# miditransformer.net
KiCad netlist of a schematic drawn in EAGLE
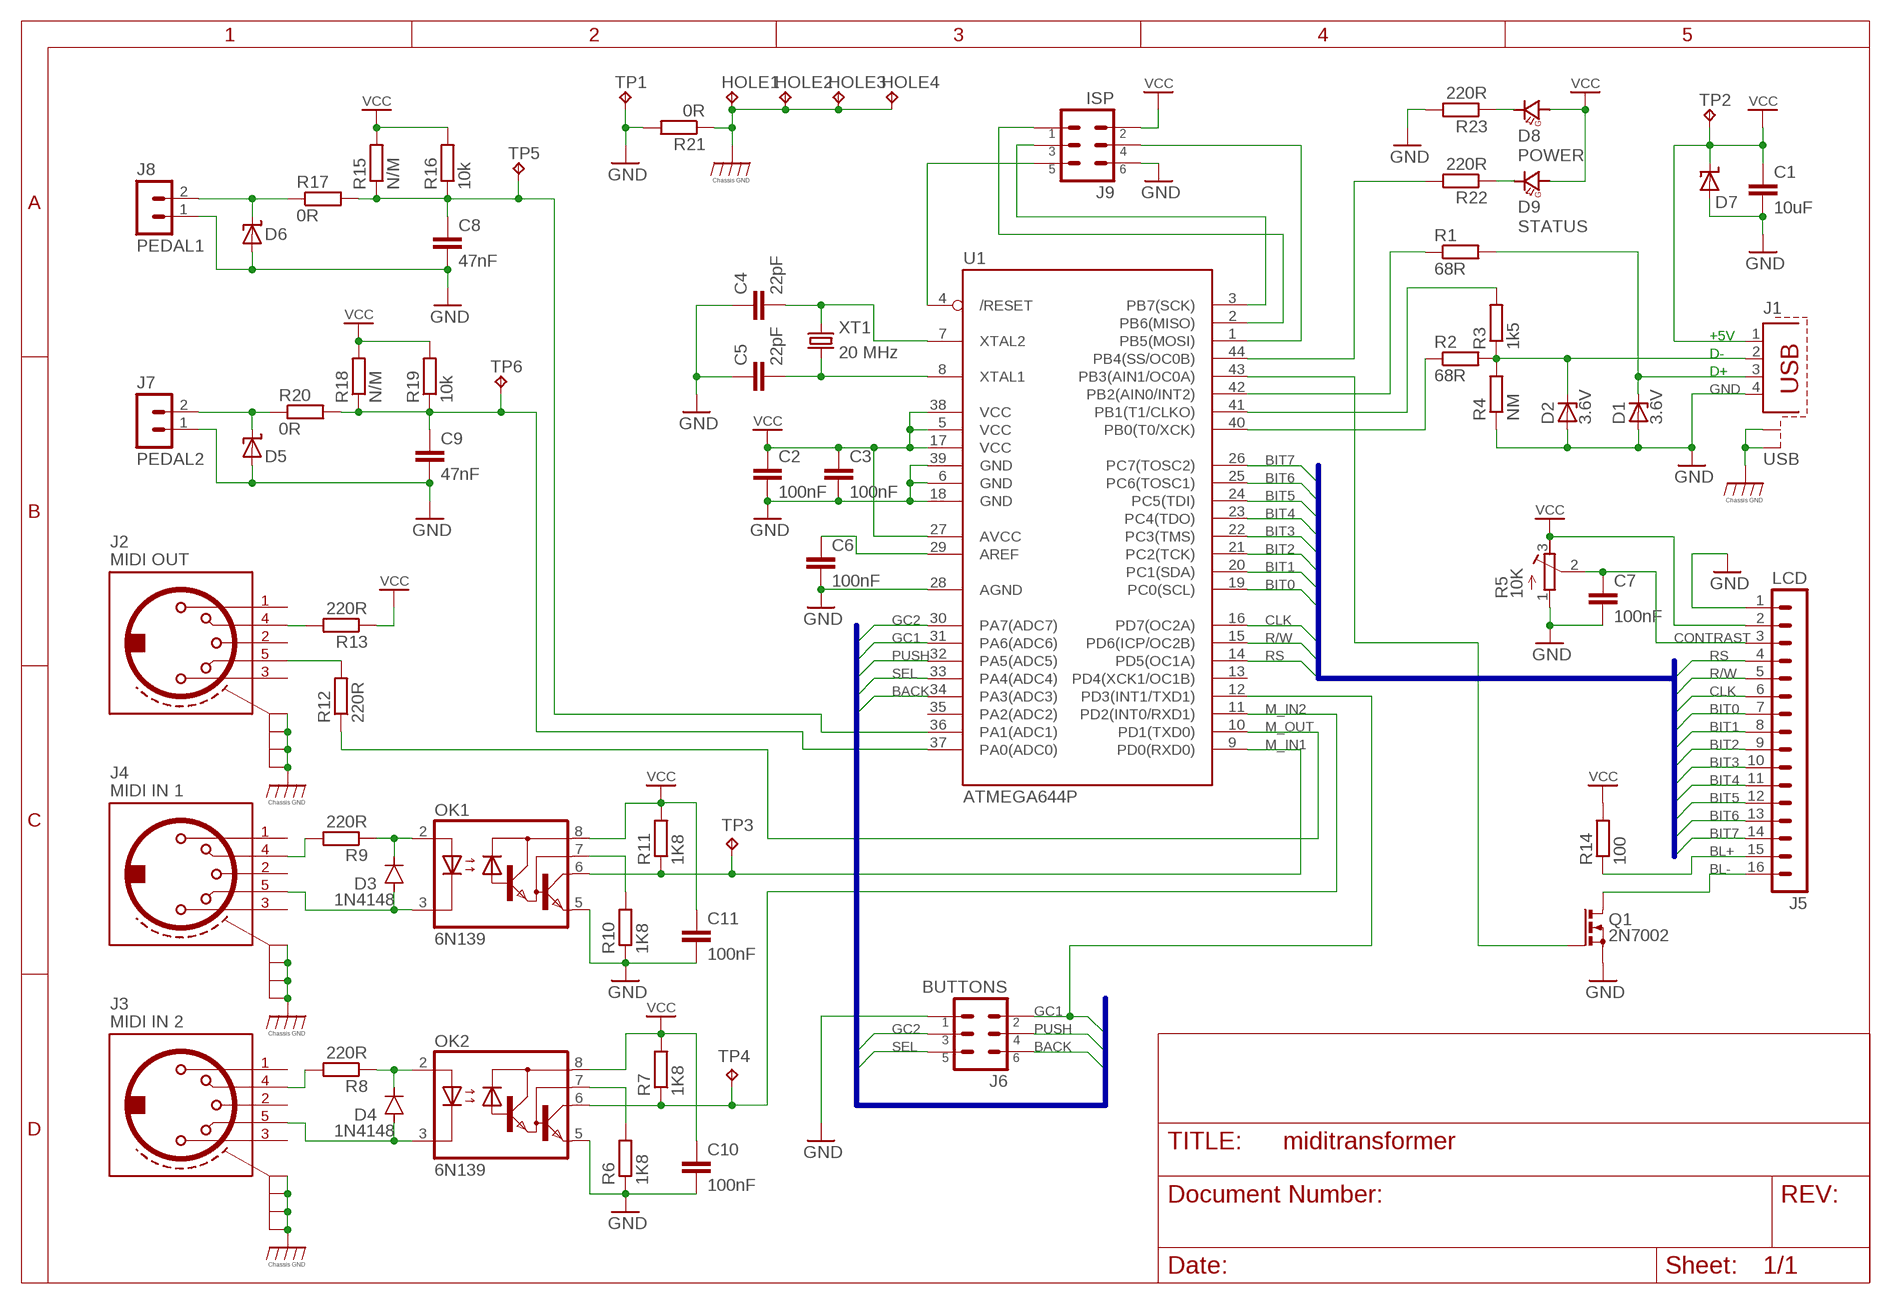
[diagram p0: schematic, sheet 1]

(export (version "E")
  (design (tool "Eeschema 10.0.6"))
  (components
    (comp (ref "C1")
      (value "10uF")
      (footprint "eagle-import:C1210")
      (libsource (lib "eagle-import") (part "C-EU_1210R"))
    )
    (comp (ref "C2")
      (value "100nF")
      (footprint "eagle-import:C0805")
      (libsource (lib "eagle-import") (part "C-EU_0805R"))
    )
    (comp (ref "C3")
      (value "100nF")
      (footprint "eagle-import:C0805")
      (libsource (lib "eagle-import") (part "C-EU_0805R"))
    )
    (comp (ref "C4")
      (value "22pF")
      (footprint "eagle-import:C0805")
      (libsource (lib "eagle-import") (part "C-EU_0805R"))
    )
    (comp (ref "C5")
      (value "22pF")
      (footprint "eagle-import:C0805")
      (libsource (lib "eagle-import") (part "C-EU_0805R"))
    )
    (comp (ref "C6")
      (value "100nF")
      (footprint "eagle-import:C0805")
      (libsource (lib "eagle-import") (part "C-EU_0805R"))
    )
    (comp (ref "C7")
      (value "100nF")
      (footprint "eagle-import:C0805")
      (libsource (lib "eagle-import") (part "C-EU_0805R"))
    )
    (comp (ref "C8")
      (value "47nF")
      (footprint "eagle-import:C0805")
      (libsource (lib "eagle-import") (part "C-EU_0805R"))
    )
    (comp (ref "C9")
      (value "47nF")
      (footprint "eagle-import:C0805")
      (libsource (lib "eagle-import") (part "C-EU_0805R"))
    )
    (comp (ref "C10")
      (value "100nF")
      (footprint "eagle-import:C0805")
      (libsource (lib "eagle-import") (part "C-EU_0805R"))
    )
    (comp (ref "C11")
      (value "100nF")
      (footprint "eagle-import:C0805")
      (libsource (lib "eagle-import") (part "C-EU_0805R"))
    )
    (comp (ref "D1")
      (value "3.6V")
      (footprint "eagle-import:DO34Z7")
      (libsource (lib "eagle-import") (part "ZENER-DIODEDO34-7"))
    )
    (comp (ref "D2")
      (value "3.6V")
      (footprint "eagle-import:DO34Z7")
      (libsource (lib "eagle-import") (part "ZENER-DIODEDO34-7"))
    )
    (comp (ref "D3")
      (value "1N4148")
      (footprint "eagle-import:MINIMELF")
      (libsource (lib "eagle-import") (part "1N4148MINIMELF"))
    )
    (comp (ref "D4")
      (value "1N4148")
      (footprint "eagle-import:MINIMELF")
      (libsource (lib "eagle-import") (part "1N4148MINIMELF"))
    )
    (comp (ref "D5")
      (value "SUPPRESSOR-SMB")
      (footprint "eagle-import:SMB")
      (libsource (lib "eagle-import") (part "SUPPRESSOR-SMB"))
    )
    (comp (ref "D6")
      (value "SUPPRESSOR-SMB")
      (footprint "eagle-import:SMB")
      (libsource (lib "eagle-import") (part "SUPPRESSOR-SMB"))
    )
    (comp (ref "D7")
      (value "SUPPRESSOR-SMB")
      (footprint "eagle-import:SMB")
      (libsource (lib "eagle-import") (part "SUPPRESSOR-SMB"))
    )
    (comp (ref "D8")
      (value "POWER")
      (footprint "eagle-import:LED3MM")
      (libsource (lib "eagle-import") (part "LTL-1CHG"))
    )
    (comp (ref "D9")
      (value "STATUS")
      (footprint "eagle-import:LED3MM")
      (libsource (lib "eagle-import") (part "LTL-1CHG"))
    )
    (comp (ref "HOLE1")
      (value "HOLE_PAD")
      (footprint "eagle-import:HOLE_PAD_3.2")
      (libsource (lib "eagle-import") (part "HOLE_PAD"))
    )
    (comp (ref "HOLE2")
      (value "HOLE_PAD")
      (footprint "eagle-import:HOLE_PAD_3.2")
      (libsource (lib "eagle-import") (part "HOLE_PAD"))
    )
    (comp (ref "HOLE3")
      (value "HOLE_PAD")
      (footprint "eagle-import:HOLE_PAD_3.2")
      (libsource (lib "eagle-import") (part "HOLE_PAD"))
    )
    (comp (ref "HOLE4")
      (value "HOLE_PAD")
      (footprint "eagle-import:HOLE_PAD_3.2")
      (libsource (lib "eagle-import") (part "HOLE_PAD"))
    )
    (comp (ref "J1")
      (value "USB")
      (footprint "eagle-import:PN61729-S")
      (libsource (lib "eagle-import") (part "PN61729-S"))
    )
    (comp (ref "J2")
      (value "MIDI OUT")
      (footprint "eagle-import:DIN5_FEM_UNIV")
      (libsource (lib "eagle-import") (part "DIN5_FEMALE_PCB"))
    )
    (comp (ref "J3")
      (value "MIDI IN 2")
      (footprint "eagle-import:DIN5_FEM_UNIV")
      (libsource (lib "eagle-import") (part "DIN5_FEMALE_PCB"))
    )
    (comp (ref "J4")
      (value "MIDI IN 1")
      (footprint "eagle-import:DIN5_FEM_UNIV")
      (libsource (lib "eagle-import") (part "DIN5_FEMALE_PCB"))
    )
    (comp (ref "J5")
      (value "LCD")
      (footprint "eagle-import:HDR_S_2X8")
      (libsource (lib "eagle-import") (part "HEADER2X8LS"))
    )
    (comp (ref "J6")
      (value "BUTTONS")
      (footprint "eagle-import:HDR_S_2X3")
      (libsource (lib "eagle-import") (part "con-head_HEADER2X3S"))
    )
    (comp (ref "J7")
      (value "PEDAL2")
      (footprint "eagle-import:MOLEX_KK_HDR2_FL")
      (libsource (lib "eagle-import") (part "HEADER1X2KK"))
    )
    (comp (ref "J8")
      (value "PEDAL1")
      (footprint "eagle-import:MOLEX_KK_HDR2_FL")
      (libsource (lib "eagle-import") (part "HEADER1X2KK"))
    )
    (comp (ref "J9")
      (value "ISP")
      (footprint "eagle-import:HDR_2X3")
      (libsource (lib "eagle-import") (part "HEADER2X3"))
    )
    (comp (ref "OK1")
      (value "6N139")
      (footprint "eagle-import:DIL08")
      (libsource (lib "eagle-import") (part "6N138DIL08"))
    )
    (comp (ref "OK2")
      (value "6N139")
      (footprint "eagle-import:DIL08")
      (libsource (lib "eagle-import") (part "6N138DIL08"))
    )
    (comp (ref "Q1")
      (value "2N7002")
      (footprint "eagle-import:SOT23")
      (libsource (lib "eagle-import") (part "2N700?2"))
    )
    (comp (ref "R1")
      (value "68R")
      (footprint "eagle-import:R0805")
      (libsource (lib "eagle-import") (part "R-EU0805"))
    )
    (comp (ref "R2")
      (value "68R")
      (footprint "eagle-import:R0805")
      (libsource (lib "eagle-import") (part "R-EU0805"))
    )
    (comp (ref "R3")
      (value "1k5")
      (footprint "eagle-import:R0805")
      (libsource (lib "eagle-import") (part "R-EU0805"))
    )
    (comp (ref "R4")
      (value "NM")
      (footprint "eagle-import:R0805")
      (libsource (lib "eagle-import") (part "R-EU0805"))
    )
    (comp (ref "R5")
      (value "10K")
      (footprint "eagle-import:RTRIM3339P")
      (libsource (lib "eagle-import") (part "R-TRIMM"))
    )
    (comp (ref "R6")
      (value "1K8")
      (footprint "eagle-import:R0805")
      (libsource (lib "eagle-import") (part "R-EU0805"))
    )
    (comp (ref "R7")
      (value "1K8")
      (footprint "eagle-import:R0805")
      (libsource (lib "eagle-import") (part "R-EU0805"))
    )
    (comp (ref "R8")
      (value "220R")
      (footprint "eagle-import:R0805")
      (libsource (lib "eagle-import") (part "R-EU0805"))
    )
    (comp (ref "R9")
      (value "220R")
      (footprint "eagle-import:R0805")
      (libsource (lib "eagle-import") (part "R-EU0805"))
    )
    (comp (ref "R10")
      (value "1K8")
      (footprint "eagle-import:R0805")
      (libsource (lib "eagle-import") (part "R-EU0805"))
    )
    (comp (ref "R11")
      (value "1K8")
      (footprint "eagle-import:R0805")
      (libsource (lib "eagle-import") (part "R-EU0805"))
    )
    (comp (ref "R12")
      (value "220R")
      (footprint "eagle-import:R0805")
      (libsource (lib "eagle-import") (part "R-EU0805"))
    )
    (comp (ref "R13")
      (value "220R")
      (footprint "eagle-import:R0805")
      (libsource (lib "eagle-import") (part "R-EU0805"))
    )
    (comp (ref "R14")
      (value "100")
      (footprint "eagle-import:0207_7")
      (libsource (lib "eagle-import") (part "R-EULEADED-7.5"))
    )
    (comp (ref "R15")
      (value "N/M")
      (footprint "eagle-import:R0805")
      (libsource (lib "eagle-import") (part "R-EU0805"))
    )
    (comp (ref "R16")
      (value "10k")
      (footprint "eagle-import:R0805")
      (libsource (lib "eagle-import") (part "R-EU0805"))
    )
    (comp (ref "R17")
      (value "0R")
      (footprint "eagle-import:R0805")
      (libsource (lib "eagle-import") (part "R-EU0805"))
    )
    (comp (ref "R18")
      (value "N/M")
      (footprint "eagle-import:R0805")
      (libsource (lib "eagle-import") (part "R-EU0805"))
    )
    (comp (ref "R19")
      (value "10k")
      (footprint "eagle-import:R0805")
      (libsource (lib "eagle-import") (part "R-EU0805"))
    )
    (comp (ref "R20")
      (value "0R")
      (footprint "eagle-import:R0805")
      (libsource (lib "eagle-import") (part "R-EU0805"))
    )
    (comp (ref "R21")
      (value "0R")
      (footprint "eagle-import:R0805")
      (libsource (lib "eagle-import") (part "R-EU0805"))
    )
    (comp (ref "R22")
      (value "220R")
      (footprint "eagle-import:R0805")
      (libsource (lib "eagle-import") (part "R-EU0805"))
    )
    (comp (ref "R23")
      (value "220R")
      (footprint "eagle-import:R0805")
      (libsource (lib "eagle-import") (part "R-EU0805"))
    )
    (comp (ref "TP1")
      (value "TPTH-15-06")
      (footprint "eagle-import:TP-TH-15-06")
      (libsource (lib "eagle-import") (part "TPTH-15-06"))
    )
    (comp (ref "TP2")
      (value "TPTH-15-06")
      (footprint "eagle-import:TP-TH-15-06")
      (libsource (lib "eagle-import") (part "TPTH-15-06"))
    )
    (comp (ref "TP3")
      (value "TPTH-15-06")
      (footprint "eagle-import:TP-TH-15-06")
      (libsource (lib "eagle-import") (part "TPTH-15-06"))
    )
    (comp (ref "TP4")
      (value "TPTH-15-06")
      (footprint "eagle-import:TP-TH-15-06")
      (libsource (lib "eagle-import") (part "TPTH-15-06"))
    )
    (comp (ref "TP5")
      (value "TPTH-15-06")
      (footprint "eagle-import:TP-TH-15-06")
      (libsource (lib "eagle-import") (part "TPTH-15-06"))
    )
    (comp (ref "TP6")
      (value "TPTH-15-06")
      (footprint "eagle-import:TP-TH-15-06")
      (libsource (lib "eagle-import") (part "TPTH-15-06"))
    )
    (comp (ref "U1")
      (value "ATMEGA644P")
      (footprint "eagle-import:TQFP44")
      (libsource (lib "eagle-import") (part "ATMEGA644P"))
    )
    (comp (ref "XT1")
      (value "20 MHz")
      (footprint "eagle-import:HC49")
      (libsource (lib "eagle-import") (part "XTAL_HC49"))
    )
  )
  (nets
    (net (code "1") (name "/BACK") (class "Default")
      (node (ref "J6") (pin "6") (pinfunction "6_6") (pintype "passive"))
      (node (ref "U1") (pin "34") (pinfunction "PA3(ADC3)_34") (pintype "bidirectional"))
    )
    (net (code "2") (name "/BIT0") (class "Default")
      (node (ref "J5") (pin "7") (pinfunction "7_7") (pintype "passive"))
      (node (ref "U1") (pin "19") (pinfunction "PC0(SCL)_19") (pintype "bidirectional"))
    )
    (net (code "3") (name "/BIT1") (class "Default")
      (node (ref "J5") (pin "8") (pinfunction "8_8") (pintype "passive"))
      (node (ref "U1") (pin "20") (pinfunction "PC1(SDA)_20") (pintype "bidirectional"))
    )
    (net (code "4") (name "/BIT2") (class "Default")
      (node (ref "J5") (pin "9") (pinfunction "9_9") (pintype "passive"))
      (node (ref "U1") (pin "21") (pinfunction "PC2(TCK)_21") (pintype "bidirectional"))
    )
    (net (code "5") (name "/BIT3") (class "Default")
      (node (ref "J5") (pin "10") (pinfunction "10_10") (pintype "passive"))
      (node (ref "U1") (pin "22") (pinfunction "PC3(TMS)_22") (pintype "bidirectional"))
    )
    (net (code "6") (name "/BIT4") (class "Default")
      (node (ref "J5") (pin "11") (pinfunction "11_11") (pintype "passive"))
      (node (ref "U1") (pin "23") (pinfunction "PC4(TDO)_23") (pintype "bidirectional"))
    )
    (net (code "7") (name "/BIT5") (class "Default")
      (node (ref "J5") (pin "12") (pinfunction "12_12") (pintype "passive"))
      (node (ref "U1") (pin "24") (pinfunction "PC5(TDI)_24") (pintype "bidirectional"))
    )
    (net (code "8") (name "/BIT6") (class "Default")
      (node (ref "J5") (pin "13") (pinfunction "13_13") (pintype "passive"))
      (node (ref "U1") (pin "25") (pinfunction "PC6(TOSC1)_25") (pintype "bidirectional"))
    )
    (net (code "9") (name "/BIT7") (class "Default")
      (node (ref "J5") (pin "14") (pinfunction "14_14") (pintype "passive"))
      (node (ref "U1") (pin "26") (pinfunction "PC7(TOSC2)_26") (pintype "bidirectional"))
    )
    (net (code "10") (name "/BL+") (class "Default")
      (node (ref "J5") (pin "15") (pinfunction "15_15") (pintype "passive"))
      (node (ref "R14") (pin "1") (pinfunction "1_1") (pintype "passive"))
    )
    (net (code "11") (name "/BL-") (class "Default")
      (node (ref "J5") (pin "16") (pinfunction "16_16") (pintype "passive"))
      (node (ref "Q1") (pin "3") (pinfunction "D_3") (pintype "passive"))
    )
    (net (code "12") (name "/CLK") (class "Default")
      (node (ref "J5") (pin "6") (pinfunction "6_6") (pintype "passive"))
      (node (ref "U1") (pin "16") (pinfunction "PD7(OC2A)_16") (pintype "bidirectional"))
    )
    (net (code "13") (name "/CONTRAST") (class "Default")
      (node (ref "C7") (pin "1") (pinfunction "1_1") (pintype "passive"))
      (node (ref "J5") (pin "3") (pinfunction "3_3") (pintype "passive"))
      (node (ref "R5") (pin "2") (pinfunction "S_2") (pintype "passive"))
    )
    (net (code "14") (name "/GC1") (class "Default")
      (node (ref "J6") (pin "2") (pinfunction "2_2") (pintype "passive"))
      (node (ref "U1") (pin "12") (pinfunction "PD3(INT1/TXD1)_12") (pintype "bidirectional"))
      (node (ref "U1") (pin "31") (pinfunction "PA6(ADC6)_31") (pintype "bidirectional"))
    )
    (net (code "15") (name "/GC2") (class "Default")
      (node (ref "J6") (pin "3") (pinfunction "3_3") (pintype "passive"))
      (node (ref "U1") (pin "30") (pinfunction "PA7(ADC7)_30") (pintype "bidirectional"))
    )
    (net (code "16") (name "/M_IN1") (class "Default")
      (node (ref "OK1") (pin "6") (pinfunction "VO_6") (pintype "passive"))
      (node (ref "R11") (pin "1") (pinfunction "1_1") (pintype "passive"))
      (node (ref "TP3") (pin "1") (pinfunction "TP_1") (pintype "input"))
      (node (ref "U1") (pin "9") (pinfunction "PD0(RXD0)_9") (pintype "bidirectional"))
    )
    (net (code "17") (name "/M_IN2") (class "Default")
      (node (ref "OK2") (pin "6") (pinfunction "VO_6") (pintype "passive"))
      (node (ref "R7") (pin "1") (pinfunction "1_1") (pintype "passive"))
      (node (ref "TP4") (pin "1") (pinfunction "TP_1") (pintype "input"))
      (node (ref "U1") (pin "11") (pinfunction "PD2(INT0/RXD1)_11") (pintype "bidirectional"))
    )
    (net (code "18") (name "/M_OUT") (class "Default")
      (node (ref "R12") (pin "1") (pinfunction "1_1") (pintype "passive"))
      (node (ref "U1") (pin "10") (pinfunction "PD1(TXD0)_10") (pintype "bidirectional"))
    )
    (net (code "19") (name "/PUSH") (class "Default")
      (node (ref "J6") (pin "4") (pinfunction "4_4") (pintype "passive"))
      (node (ref "U1") (pin "32") (pinfunction "PA5(ADC5)_32") (pintype "bidirectional"))
    )
    (net (code "20") (name "/RS") (class "Default")
      (node (ref "J5") (pin "4") (pinfunction "4_4") (pintype "passive"))
      (node (ref "U1") (pin "14") (pinfunction "PD5(OC1A)_14") (pintype "bidirectional"))
    )
    (net (code "21") (name "/R{slash}W") (class "Default")
      (node (ref "J5") (pin "5") (pinfunction "5_5") (pintype "passive"))
      (node (ref "U1") (pin "15") (pinfunction "PD6(ICP/OC2B)_15") (pintype "bidirectional"))
    )
    (net (code "22") (name "/SEL") (class "Default")
      (node (ref "J6") (pin "5") (pinfunction "5_5") (pintype "passive"))
      (node (ref "U1") (pin "33") (pinfunction "PA4(ADC4)_33") (pintype "bidirectional"))
    )
    (net (code "23") (name "CGND") (class "Default")
      (node (ref "HOLE1") (pin "P$0") (pinfunction "TP_P$0") (pintype "input"))
      (node (ref "HOLE2") (pin "P$0") (pinfunction "TP_P$0") (pintype "input"))
      (node (ref "HOLE3") (pin "P$0") (pinfunction "TP_P$0") (pintype "input"))
      (node (ref "HOLE4") (pin "P$0") (pinfunction "TP_P$0") (pintype "input"))
      (node (ref "J1") (pin "S1") (pinfunction "S1_S1") (pintype "passive"))
      (node (ref "J1") (pin "S2") (pinfunction "S2_S2") (pintype "passive"))
      (node (ref "J2") (pin "PE@1") (pinfunction "PE_PE@1") (pintype "power_in"))
      (node (ref "J2") (pin "PE@2") (pinfunction "PE_PE@2") (pintype "power_in"))
      (node (ref "J2") (pin "PE@3") (pinfunction "PE_PE@3") (pintype "power_in"))
      (node (ref "J2") (pin "PE@4") (pinfunction "PE_PE@4") (pintype "power_in"))
      (node (ref "J3") (pin "PE@1") (pinfunction "PE_PE@1") (pintype "power_in"))
      (node (ref "J3") (pin "PE@2") (pinfunction "PE_PE@2") (pintype "power_in"))
      (node (ref "J3") (pin "PE@3") (pinfunction "PE_PE@3") (pintype "power_in"))
      (node (ref "J3") (pin "PE@4") (pinfunction "PE_PE@4") (pintype "power_in"))
      (node (ref "J4") (pin "PE@1") (pinfunction "PE_PE@1") (pintype "power_in"))
      (node (ref "J4") (pin "PE@2") (pinfunction "PE_PE@2") (pintype "power_in"))
      (node (ref "J4") (pin "PE@3") (pinfunction "PE_PE@3") (pintype "power_in"))
      (node (ref "J4") (pin "PE@4") (pinfunction "PE_PE@4") (pintype "power_in"))
      (node (ref "R21") (pin "1") (pinfunction "1_1") (pintype "passive"))
    )
    (net (code "24") (name "GND") (class "Default")
      (node (ref "C1") (pin "2") (pinfunction "2_2") (pintype "passive"))
      (node (ref "C10") (pin "2") (pinfunction "2_2") (pintype "passive"))
      (node (ref "C11") (pin "2") (pinfunction "2_2") (pintype "passive"))
      (node (ref "C2") (pin "2") (pinfunction "2_2") (pintype "passive"))
      (node (ref "C3") (pin "2") (pinfunction "2_2") (pintype "passive"))
      (node (ref "C4") (pin "1") (pinfunction "1_1") (pintype "passive"))
      (node (ref "C5") (pin "1") (pinfunction "1_1") (pintype "passive"))
      (node (ref "C6") (pin "2") (pinfunction "2_2") (pintype "passive"))
      (node (ref "C7") (pin "2") (pinfunction "2_2") (pintype "passive"))
      (node (ref "C8") (pin "2") (pinfunction "2_2") (pintype "passive"))
      (node (ref "C9") (pin "2") (pinfunction "2_2") (pintype "passive"))
      (node (ref "D1") (pin "A") (pinfunction "A_A") (pintype "passive"))
      (node (ref "D2") (pin "A") (pinfunction "A_A") (pintype "passive"))
      (node (ref "D5") (pin "A") (pinfunction "A_A") (pintype "passive"))
      (node (ref "D6") (pin "A") (pinfunction "A_A") (pintype "passive"))
      (node (ref "D7") (pin "A") (pinfunction "A_A") (pintype "passive"))
      (node (ref "J1") (pin "4") (pinfunction "4_4") (pintype "passive"))
      (node (ref "J5") (pin "1") (pinfunction "1_1") (pintype "passive"))
      (node (ref "J6") (pin "1") (pinfunction "1_1") (pintype "passive"))
      (node (ref "J7") (pin "1") (pinfunction "1_1") (pintype "passive"))
      (node (ref "J8") (pin "1") (pinfunction "1_1") (pintype "passive"))
      (node (ref "J9") (pin "6") (pinfunction "6_6") (pintype "passive"))
      (node (ref "OK1") (pin "5") (pinfunction "GND_5") (pintype "passive"))
      (node (ref "OK2") (pin "5") (pinfunction "GND_5") (pintype "passive"))
      (node (ref "Q1") (pin "2") (pinfunction "S_2") (pintype "passive"))
      (node (ref "R10") (pin "1") (pinfunction "1_1") (pintype "passive"))
      (node (ref "R21") (pin "2") (pinfunction "2_2") (pintype "passive"))
      (node (ref "R23") (pin "2") (pinfunction "2_2") (pintype "passive"))
      (node (ref "R4") (pin "1") (pinfunction "1_1") (pintype "passive"))
      (node (ref "R5") (pin "1") (pinfunction "E_1") (pintype "passive"))
      (node (ref "R6") (pin "1") (pinfunction "1_1") (pintype "passive"))
      (node (ref "TP1") (pin "1") (pinfunction "TP_1") (pintype "input"))
      (node (ref "U1") (pin "18") (pinfunction "GND_18") (pintype "power_in"))
      (node (ref "U1") (pin "28") (pinfunction "AGND_28") (pintype "power_in"))
      (node (ref "U1") (pin "39") (pinfunction "GND_39") (pintype "power_in"))
      (node (ref "U1") (pin "6") (pinfunction "GND_6") (pintype "power_in"))
    )
    (net (code "25") (name "Net-(D1-PadC)") (class "Default")
      (node (ref "D1") (pin "C") (pinfunction "C_C") (pintype "passive"))
      (node (ref "J1") (pin "3") (pinfunction "3_3") (pintype "passive"))
      (node (ref "R1") (pin "2") (pinfunction "2_2") (pintype "passive"))
    )
    (net (code "26") (name "Net-(D2-PadC)") (class "Default")
      (node (ref "D2") (pin "C") (pinfunction "C_C") (pintype "passive"))
      (node (ref "J1") (pin "2") (pinfunction "2_2") (pintype "passive"))
      (node (ref "R2") (pin "2") (pinfunction "2_2") (pintype "passive"))
      (node (ref "R3") (pin "1") (pinfunction "1_1") (pintype "passive"))
      (node (ref "R4") (pin "2") (pinfunction "2_2") (pintype "passive"))
    )
    (net (code "27") (name "Net-(D5-PadC)") (class "Default")
      (node (ref "D5") (pin "C") (pinfunction "C_C") (pintype "passive"))
      (node (ref "J7") (pin "2") (pinfunction "2_2") (pintype "passive"))
      (node (ref "R20") (pin "1") (pinfunction "1_1") (pintype "passive"))
    )
    (net (code "28") (name "Net-(D6-PadC)") (class "Default")
      (node (ref "D6") (pin "C") (pinfunction "C_C") (pintype "passive"))
      (node (ref "J8") (pin "2") (pinfunction "2_2") (pintype "passive"))
      (node (ref "R17") (pin "1") (pinfunction "1_1") (pintype "passive"))
    )
    (net (code "29") (name "Net-(D8-PadC)") (class "Default")
      (node (ref "D8") (pin "C") (pinfunction "C_C") (pintype "passive"))
      (node (ref "R23") (pin "1") (pinfunction "1_1") (pintype "passive"))
    )
    (net (code "30") (name "Net-(D9-PadC)") (class "Default")
      (node (ref "D9") (pin "C") (pinfunction "C_C") (pintype "passive"))
      (node (ref "R22") (pin "1") (pinfunction "1_1") (pintype "passive"))
    )
    (net (code "31") (name "Net-(J2-Pad4)") (class "Default")
      (node (ref "J2") (pin "4") (pinfunction "4_4") (pintype "passive"))
      (node (ref "R13") (pin "2") (pinfunction "2_2") (pintype "passive"))
    )
    (net (code "32") (name "Net-(J2-Pad5)") (class "Default")
      (node (ref "J2") (pin "5") (pinfunction "5_5") (pintype "passive"))
      (node (ref "R12") (pin "2") (pinfunction "2_2") (pintype "passive"))
    )
    (net (code "33") (name "Net-(J3-Pad4)") (class "Default")
      (node (ref "J3") (pin "4") (pinfunction "4_4") (pintype "passive"))
      (node (ref "R8") (pin "2") (pinfunction "2_2") (pintype "passive"))
    )
    (net (code "34") (name "Net-(J4-Pad4)") (class "Default")
      (node (ref "J4") (pin "4") (pinfunction "4_4") (pintype "passive"))
      (node (ref "R9") (pin "2") (pinfunction "2_2") (pintype "passive"))
    )
    (net (code "35") (name "Net-(OK1-A)") (class "Default")
      (node (ref "D3") (pin "C") (pinfunction "C_C") (pintype "passive"))
      (node (ref "OK1") (pin "2") (pinfunction "A_2") (pintype "passive"))
      (node (ref "R9") (pin "1") (pinfunction "1_1") (pintype "passive"))
    )
    (net (code "36") (name "Net-(OK1-C)") (class "Default")
      (node (ref "D3") (pin "A") (pinfunction "A_A") (pintype "passive"))
      (node (ref "J4") (pin "5") (pinfunction "5_5") (pintype "passive"))
      (node (ref "OK1") (pin "3") (pinfunction "C_3") (pintype "passive"))
    )
    (net (code "37") (name "Net-(OK1-VB)") (class "Default")
      (node (ref "OK1") (pin "7") (pinfunction "VB_7") (pintype "passive"))
      (node (ref "R10") (pin "2") (pinfunction "2_2") (pintype "passive"))
    )
    (net (code "38") (name "Net-(OK2-A)") (class "Default")
      (node (ref "D4") (pin "C") (pinfunction "C_C") (pintype "passive"))
      (node (ref "OK2") (pin "2") (pinfunction "A_2") (pintype "passive"))
      (node (ref "R8") (pin "1") (pinfunction "1_1") (pintype "passive"))
    )
    (net (code "39") (name "Net-(OK2-C)") (class "Default")
      (node (ref "D4") (pin "A") (pinfunction "A_A") (pintype "passive"))
      (node (ref "J3") (pin "5") (pinfunction "5_5") (pintype "passive"))
      (node (ref "OK2") (pin "3") (pinfunction "C_3") (pintype "passive"))
    )
    (net (code "40") (name "Net-(OK2-VB)") (class "Default")
      (node (ref "OK2") (pin "7") (pinfunction "VB_7") (pintype "passive"))
      (node (ref "R6") (pin "2") (pinfunction "2_2") (pintype "passive"))
    )
    (net (code "41") (name "Net-(Q1-G)") (class "Default")
      (node (ref "Q1") (pin "1") (pinfunction "G_1") (pintype "passive"))
      (node (ref "U1") (pin "43") (pinfunction "PB3(AIN1/OC0A)_43") (pintype "bidirectional"))
    )
    (net (code "42") (name "Net-(TP5-TP)") (class "Default")
      (node (ref "C8") (pin "1") (pinfunction "1_1") (pintype "passive"))
      (node (ref "R15") (pin "1") (pinfunction "1_1") (pintype "passive"))
      (node (ref "R16") (pin "1") (pinfunction "1_1") (pintype "passive"))
      (node (ref "R17") (pin "2") (pinfunction "2_2") (pintype "passive"))
      (node (ref "TP5") (pin "1") (pinfunction "TP_1") (pintype "input"))
      (node (ref "U1") (pin "36") (pinfunction "PA1(ADC1)_36") (pintype "bidirectional"))
    )
    (net (code "43") (name "Net-(TP6-TP)") (class "Default")
      (node (ref "C9") (pin "1") (pinfunction "1_1") (pintype "passive"))
      (node (ref "R18") (pin "1") (pinfunction "1_1") (pintype "passive"))
      (node (ref "R19") (pin "1") (pinfunction "1_1") (pintype "passive"))
      (node (ref "R20") (pin "2") (pinfunction "2_2") (pintype "passive"))
      (node (ref "TP6") (pin "1") (pinfunction "TP_1") (pintype "input"))
      (node (ref "U1") (pin "37") (pinfunction "PA0(ADC0)_37") (pintype "bidirectional"))
    )
    (net (code "44") (name "Net-(U1-AREF)") (class "Default")
      (node (ref "C6") (pin "1") (pinfunction "1_1") (pintype "passive"))
      (node (ref "U1") (pin "29") (pinfunction "AREF_29") (pintype "power_in"))
    )
    (net (code "45") (name "Net-(U1-PB0(T0{slash}XCK))") (class "Default")
      (node (ref "R2") (pin "1") (pinfunction "1_1") (pintype "passive"))
      (node (ref "U1") (pin "40") (pinfunction "PB0(T0/XCK)_40") (pintype "bidirectional"))
    )
    (net (code "46") (name "Net-(U1-PB1(T1{slash}CLKO))") (class "Default")
      (node (ref "R3") (pin "2") (pinfunction "2_2") (pintype "passive"))
      (node (ref "U1") (pin "41") (pinfunction "PB1(T1/CLKO)_41") (pintype "bidirectional"))
    )
    (net (code "47") (name "Net-(U1-PB2(AIN0{slash}INT2))") (class "Default")
      (node (ref "R1") (pin "1") (pinfunction "1_1") (pintype "passive"))
      (node (ref "U1") (pin "42") (pinfunction "PB2(AIN0/INT2)_42") (pintype "bidirectional"))
    )
    (net (code "48") (name "Net-(U1-PB4(SS{slash}OC0B))") (class "Default")
      (node (ref "R22") (pin "2") (pinfunction "2_2") (pintype "passive"))
      (node (ref "U1") (pin "44") (pinfunction "PB4(SS/OC0B)_44") (pintype "bidirectional"))
    )
    (net (code "49") (name "Net-(U1-PB5(MOSI))") (class "Default")
      (node (ref "J9") (pin "4") (pinfunction "4_4") (pintype "passive"))
      (node (ref "U1") (pin "1") (pinfunction "PB5(MOSI)_1") (pintype "bidirectional"))
    )
    (net (code "50") (name "Net-(U1-PB6(MISO))") (class "Default")
      (node (ref "J9") (pin "1") (pinfunction "1_1") (pintype "passive"))
      (node (ref "U1") (pin "2") (pinfunction "PB6(MISO)_2") (pintype "bidirectional"))
    )
    (net (code "51") (name "Net-(U1-PB7(SCK))") (class "Default")
      (node (ref "J9") (pin "3") (pinfunction "3_3") (pintype "passive"))
      (node (ref "U1") (pin "3") (pinfunction "PB7(SCK)_3") (pintype "bidirectional"))
    )
    (net (code "52") (name "Net-(U1-XTAL1)") (class "Default")
      (node (ref "C5") (pin "2") (pinfunction "2_2") (pintype "passive"))
      (node (ref "U1") (pin "8") (pinfunction "XTAL1_8") (pintype "bidirectional"))
      (node (ref "XT1") (pin "2") (pinfunction "2_2") (pintype "passive"))
    )
    (net (code "53") (name "Net-(U1-XTAL2)") (class "Default")
      (node (ref "C4") (pin "2") (pinfunction "2_2") (pintype "passive"))
      (node (ref "U1") (pin "7") (pinfunction "XTAL2_7") (pintype "bidirectional"))
      (node (ref "XT1") (pin "1") (pinfunction "1_1") (pintype "passive"))
    )
    (net (code "54") (name "Net-(U1-{slash}RESET)") (class "Default")
      (node (ref "J9") (pin "5") (pinfunction "5_5") (pintype "passive"))
      (node (ref "U1") (pin "4") (pinfunction "/RESET_4") (pintype "input"))
    )
    (net (code "55") (name "VCC") (class "Default")
      (node (ref "C1") (pin "1") (pinfunction "1_1") (pintype "passive"))
      (node (ref "C10") (pin "1") (pinfunction "1_1") (pintype "passive"))
      (node (ref "C11") (pin "1") (pinfunction "1_1") (pintype "passive"))
      (node (ref "C2") (pin "1") (pinfunction "1_1") (pintype "passive"))
      (node (ref "C3") (pin "1") (pinfunction "1_1") (pintype "passive"))
      (node (ref "D7") (pin "C") (pinfunction "C_C") (pintype "passive"))
      (node (ref "D8") (pin "A") (pinfunction "A_A") (pintype "passive"))
      (node (ref "D9") (pin "A") (pinfunction "A_A") (pintype "passive"))
      (node (ref "J1") (pin "1") (pinfunction "1_1") (pintype "passive"))
      (node (ref "J5") (pin "2") (pinfunction "2_2") (pintype "passive"))
      (node (ref "J9") (pin "2") (pinfunction "2_2") (pintype "passive"))
      (node (ref "OK1") (pin "8") (pinfunction "VCC_8") (pintype "passive"))
      (node (ref "OK2") (pin "8") (pinfunction "VCC_8") (pintype "passive"))
      (node (ref "R11") (pin "2") (pinfunction "2_2") (pintype "passive"))
      (node (ref "R13") (pin "1") (pinfunction "1_1") (pintype "passive"))
      (node (ref "R14") (pin "2") (pinfunction "2_2") (pintype "passive"))
      (node (ref "R15") (pin "2") (pinfunction "2_2") (pintype "passive"))
      (node (ref "R16") (pin "2") (pinfunction "2_2") (pintype "passive"))
      (node (ref "R18") (pin "2") (pinfunction "2_2") (pintype "passive"))
      (node (ref "R19") (pin "2") (pinfunction "2_2") (pintype "passive"))
      (node (ref "R5") (pin "3") (pinfunction "A_3") (pintype "passive"))
      (node (ref "R7") (pin "2") (pinfunction "2_2") (pintype "passive"))
      (node (ref "TP2") (pin "1") (pinfunction "TP_1") (pintype "input"))
      (node (ref "U1") (pin "17") (pinfunction "VCC_17") (pintype "power_in"))
      (node (ref "U1") (pin "27") (pinfunction "AVCC_27") (pintype "power_in"))
      (node (ref "U1") (pin "38") (pinfunction "VCC_38") (pintype "power_in"))
      (node (ref "U1") (pin "5") (pinfunction "VCC_5") (pintype "power_in"))
    )
    (net (code "56") (name "unconnected-(J2-Pad1)") (class "Default")
      (node (ref "J2") (pin "1") (pinfunction "1_1") (pintype "passive"))
    )
    (net (code "57") (name "unconnected-(J2-Pad2)") (class "Default")
      (node (ref "J2") (pin "2") (pinfunction "2_2") (pintype "passive"))
    )
    (net (code "58") (name "unconnected-(J2-Pad3)") (class "Default")
      (node (ref "J2") (pin "3") (pinfunction "3_3") (pintype "passive"))
    )
    (net (code "59") (name "unconnected-(J3-Pad1)") (class "Default")
      (node (ref "J3") (pin "1") (pinfunction "1_1") (pintype "passive"))
    )
    (net (code "60") (name "unconnected-(J3-Pad2)") (class "Default")
      (node (ref "J3") (pin "2") (pinfunction "2_2") (pintype "passive"))
    )
    (net (code "61") (name "unconnected-(J3-Pad3)") (class "Default")
      (node (ref "J3") (pin "3") (pinfunction "3_3") (pintype "passive"))
    )
    (net (code "62") (name "unconnected-(J4-Pad1)") (class "Default")
      (node (ref "J4") (pin "1") (pinfunction "1_1") (pintype "passive"))
    )
    (net (code "63") (name "unconnected-(J4-Pad2)") (class "Default")
      (node (ref "J4") (pin "2") (pinfunction "2_2") (pintype "passive"))
    )
    (net (code "64") (name "unconnected-(J4-Pad3)") (class "Default")
      (node (ref "J4") (pin "3") (pinfunction "3_3") (pintype "passive"))
    )
    (net (code "65") (name "unconnected-(U1-PA2(ADC2)-Pad35)") (class "Default")
      (node (ref "U1") (pin "35") (pinfunction "PA2(ADC2)_35") (pintype "bidirectional"))
    )
    (net (code "66") (name "unconnected-(U1-PD4(XCK1{slash}OC1B)-Pad13)") (class "Default")
      (node (ref "U1") (pin "13") (pinfunction "PD4(XCK1/OC1B)_13") (pintype "bidirectional"))
    )
  )
)
